# Day.net
KiCad netlist of a schematic drawn in Altium Designer
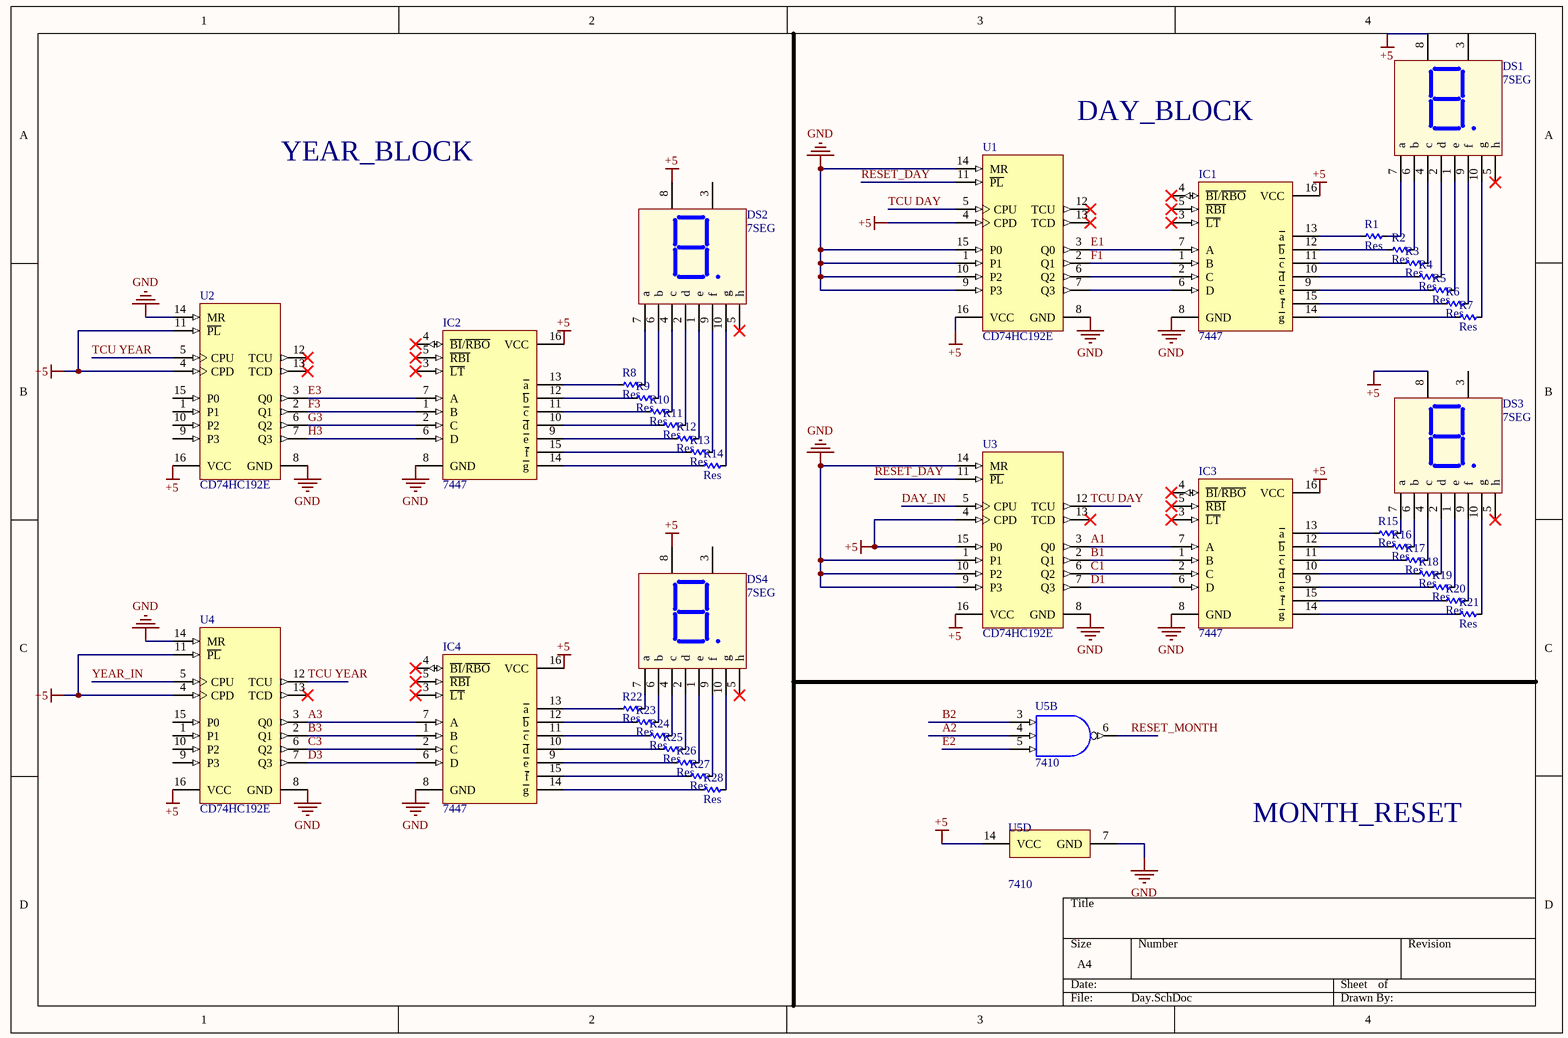
[diagram p0: Day.SchDoc]

(export (version "E")
  (design (tool "Eeschema 10.0.6"))
  (components
    (comp (ref "DS1")
      (value "7SEG")
      (footprint "LED7SEG-1-0.56")
      (description "14.2 mm General Purpose Blue 7-Segment Display: CC, RH DP, Gray Surface")
      (fields (field (name "PUBLISHER") "Altium Limited"))
      (libsource (lib "Clock_Schlib1") (part "LED7SEG-1"))
    )
    (comp (ref "DS2")
      (value "7SEG")
      (footprint "LED7SEG-1-0.56")
      (description "14.2 mm General Purpose Blue 7-Segment Display: CC, RH DP, Gray Surface")
      (fields (field (name "PUBLISHER") "Altium Limited"))
      (libsource (lib "Clock_Schlib1") (part "LED7SEG-1"))
    )
    (comp (ref "DS3")
      (value "7SEG")
      (footprint "LED7SEG-1-0.56")
      (description "14.2 mm General Purpose Blue 7-Segment Display: CC, RH DP, Gray Surface")
      (fields (field (name "PUBLISHER") "Altium Limited"))
      (libsource (lib "Clock_Schlib1") (part "LED7SEG-1"))
    )
    (comp (ref "DS4")
      (value "7SEG")
      (footprint "LED7SEG-1-0.56")
      (description "14.2 mm General Purpose Blue 7-Segment Display: CC, RH DP, Gray Surface")
      (fields (field (name "PUBLISHER") "Altium Limited"))
      (libsource (lib "Clock_Schlib1") (part "LED7SEG-1"))
    )
    (comp (ref "IC1")
      (value "7447")
      (footprint "DIP16")
      (description "BCD to 7-Segment Decoder/Driver")
      (libsource (lib "Clock_Schlib1") (part "7447"))
    )
    (comp (ref "IC2")
      (value "7447")
      (footprint "DIP16")
      (description "BCD to 7-Segment Decoder/Driver")
      (libsource (lib "Clock_Schlib1") (part "7447"))
    )
    (comp (ref "IC3")
      (value "7447")
      (footprint "DIP16")
      (description "BCD to 7-Segment Decoder/Driver")
      (libsource (lib "Clock_Schlib1") (part "7447"))
    )
    (comp (ref "IC4")
      (value "7447")
      (footprint "DIP16")
      (description "BCD to 7-Segment Decoder/Driver")
      (libsource (lib "Clock_Schlib1") (part "7447"))
    )
    (comp (ref "R1")
      (value "Res")
      (footprint "RES-1/4W")
      (fields
        (field (name "MANUFACTURER") "Generic Components")
        (field (name "PUBLISHER") "Altium Hobart Technology Centre")
      )
      (libsource (lib "Clock_Schlib1") (part "Res"))
    )
    (comp (ref "R2")
      (value "Res")
      (footprint "RES-1/4W")
      (fields
        (field (name "MANUFACTURER") "Generic Components")
        (field (name "PUBLISHER") "Altium Hobart Technology Centre")
      )
      (libsource (lib "Clock_Schlib1") (part "Res"))
    )
    (comp (ref "R3")
      (value "Res")
      (footprint "RES-1/4W")
      (fields
        (field (name "MANUFACTURER") "Generic Components")
        (field (name "PUBLISHER") "Altium Hobart Technology Centre")
      )
      (libsource (lib "Clock_Schlib1") (part "Res"))
    )
    (comp (ref "R4")
      (value "Res")
      (footprint "RES-1/4W")
      (fields
        (field (name "MANUFACTURER") "Generic Components")
        (field (name "PUBLISHER") "Altium Hobart Technology Centre")
      )
      (libsource (lib "Clock_Schlib1") (part "Res"))
    )
    (comp (ref "R5")
      (value "Res")
      (footprint "RES-1/4W")
      (fields
        (field (name "MANUFACTURER") "Generic Components")
        (field (name "PUBLISHER") "Altium Hobart Technology Centre")
      )
      (libsource (lib "Clock_Schlib1") (part "Res"))
    )
    (comp (ref "R6")
      (value "Res")
      (footprint "RES-1/4W")
      (fields
        (field (name "MANUFACTURER") "Generic Components")
        (field (name "PUBLISHER") "Altium Hobart Technology Centre")
      )
      (libsource (lib "Clock_Schlib1") (part "Res"))
    )
    (comp (ref "R7")
      (value "Res")
      (footprint "RES-1/4W")
      (fields
        (field (name "MANUFACTURER") "Generic Components")
        (field (name "PUBLISHER") "Altium Hobart Technology Centre")
      )
      (libsource (lib "Clock_Schlib1") (part "Res"))
    )
    (comp (ref "R8")
      (value "Res")
      (footprint "RES-1/4W")
      (fields
        (field (name "MANUFACTURER") "Generic Components")
        (field (name "PUBLISHER") "Altium Hobart Technology Centre")
      )
      (libsource (lib "Clock_Schlib1") (part "Res"))
    )
    (comp (ref "R9")
      (value "Res")
      (footprint "RES-1/4W")
      (fields
        (field (name "MANUFACTURER") "Generic Components")
        (field (name "PUBLISHER") "Altium Hobart Technology Centre")
      )
      (libsource (lib "Clock_Schlib1") (part "Res"))
    )
    (comp (ref "R10")
      (value "Res")
      (footprint "RES-1/4W")
      (fields
        (field (name "MANUFACTURER") "Generic Components")
        (field (name "PUBLISHER") "Altium Hobart Technology Centre")
      )
      (libsource (lib "Clock_Schlib1") (part "Res"))
    )
    (comp (ref "R11")
      (value "Res")
      (footprint "RES-1/4W")
      (fields
        (field (name "MANUFACTURER") "Generic Components")
        (field (name "PUBLISHER") "Altium Hobart Technology Centre")
      )
      (libsource (lib "Clock_Schlib1") (part "Res"))
    )
    (comp (ref "R12")
      (value "Res")
      (footprint "RES-1/4W")
      (fields
        (field (name "MANUFACTURER") "Generic Components")
        (field (name "PUBLISHER") "Altium Hobart Technology Centre")
      )
      (libsource (lib "Clock_Schlib1") (part "Res"))
    )
    (comp (ref "R13")
      (value "Res")
      (footprint "RES-1/4W")
      (fields
        (field (name "MANUFACTURER") "Generic Components")
        (field (name "PUBLISHER") "Altium Hobart Technology Centre")
      )
      (libsource (lib "Clock_Schlib1") (part "Res"))
    )
    (comp (ref "R14")
      (value "Res")
      (footprint "RES-1/4W")
      (fields
        (field (name "MANUFACTURER") "Generic Components")
        (field (name "PUBLISHER") "Altium Hobart Technology Centre")
      )
      (libsource (lib "Clock_Schlib1") (part "Res"))
    )
    (comp (ref "R15")
      (value "Res")
      (footprint "RES-1/4W")
      (fields
        (field (name "MANUFACTURER") "Generic Components")
        (field (name "PUBLISHER") "Altium Hobart Technology Centre")
      )
      (libsource (lib "Clock_Schlib1") (part "Res"))
    )
    (comp (ref "R16")
      (value "Res")
      (footprint "RES-1/4W")
      (fields
        (field (name "MANUFACTURER") "Generic Components")
        (field (name "PUBLISHER") "Altium Hobart Technology Centre")
      )
      (libsource (lib "Clock_Schlib1") (part "Res"))
    )
    (comp (ref "R17")
      (value "Res")
      (footprint "RES-1/4W")
      (fields
        (field (name "MANUFACTURER") "Generic Components")
        (field (name "PUBLISHER") "Altium Hobart Technology Centre")
      )
      (libsource (lib "Clock_Schlib1") (part "Res"))
    )
    (comp (ref "R18")
      (value "Res")
      (footprint "RES-1/4W")
      (fields
        (field (name "MANUFACTURER") "Generic Components")
        (field (name "PUBLISHER") "Altium Hobart Technology Centre")
      )
      (libsource (lib "Clock_Schlib1") (part "Res"))
    )
    (comp (ref "R19")
      (value "Res")
      (footprint "RES-1/4W")
      (fields
        (field (name "MANUFACTURER") "Generic Components")
        (field (name "PUBLISHER") "Altium Hobart Technology Centre")
      )
      (libsource (lib "Clock_Schlib1") (part "Res"))
    )
    (comp (ref "R20")
      (value "Res")
      (footprint "RES-1/4W")
      (fields
        (field (name "MANUFACTURER") "Generic Components")
        (field (name "PUBLISHER") "Altium Hobart Technology Centre")
      )
      (libsource (lib "Clock_Schlib1") (part "Res"))
    )
    (comp (ref "R21")
      (value "Res")
      (footprint "RES-1/4W")
      (fields
        (field (name "MANUFACTURER") "Generic Components")
        (field (name "PUBLISHER") "Altium Hobart Technology Centre")
      )
      (libsource (lib "Clock_Schlib1") (part "Res"))
    )
    (comp (ref "R22")
      (value "Res")
      (footprint "RES-1/4W")
      (fields
        (field (name "MANUFACTURER") "Generic Components")
        (field (name "PUBLISHER") "Altium Hobart Technology Centre")
      )
      (libsource (lib "Clock_Schlib1") (part "Res"))
    )
    (comp (ref "R23")
      (value "Res")
      (footprint "RES-1/4W")
      (fields
        (field (name "MANUFACTURER") "Generic Components")
        (field (name "PUBLISHER") "Altium Hobart Technology Centre")
      )
      (libsource (lib "Clock_Schlib1") (part "Res"))
    )
    (comp (ref "R24")
      (value "Res")
      (footprint "RES-1/4W")
      (fields
        (field (name "MANUFACTURER") "Generic Components")
        (field (name "PUBLISHER") "Altium Hobart Technology Centre")
      )
      (libsource (lib "Clock_Schlib1") (part "Res"))
    )
    (comp (ref "R25")
      (value "Res")
      (footprint "RES-1/4W")
      (fields
        (field (name "MANUFACTURER") "Generic Components")
        (field (name "PUBLISHER") "Altium Hobart Technology Centre")
      )
      (libsource (lib "Clock_Schlib1") (part "Res"))
    )
    (comp (ref "R26")
      (value "Res")
      (footprint "RES-1/4W")
      (fields
        (field (name "MANUFACTURER") "Generic Components")
        (field (name "PUBLISHER") "Altium Hobart Technology Centre")
      )
      (libsource (lib "Clock_Schlib1") (part "Res"))
    )
    (comp (ref "R27")
      (value "Res")
      (footprint "RES-1/4W")
      (fields
        (field (name "MANUFACTURER") "Generic Components")
        (field (name "PUBLISHER") "Altium Hobart Technology Centre")
      )
      (libsource (lib "Clock_Schlib1") (part "Res"))
    )
    (comp (ref "R28")
      (value "Res")
      (footprint "RES-1/4W")
      (fields
        (field (name "MANUFACTURER") "Generic Components")
        (field (name "PUBLISHER") "Altium Hobart Technology Centre")
      )
      (libsource (lib "Clock_Schlib1") (part "Res"))
    )
    (comp (ref "U1")
      (value "CD74HC192E")
      (footprint "N0016A")
      (fields
        (field (name "GENERIC PART NUMBER") "CD74HC192")
        (field (name "MANUFACTURER") "Texas Instruments")
      )
      (libsource (lib "Clock_Schlib1") (part "74192"))
    )
    (comp (ref "U2")
      (value "CD74HC192E")
      (footprint "N0016A")
      (fields
        (field (name "GENERIC PART NUMBER") "CD74HC192")
        (field (name "MANUFACTURER") "Texas Instruments")
      )
      (libsource (lib "Clock_Schlib1") (part "74192"))
    )
    (comp (ref "U3")
      (value "CD74HC192E")
      (footprint "N0016A")
      (fields
        (field (name "GENERIC PART NUMBER") "CD74HC192")
        (field (name "MANUFACTURER") "Texas Instruments")
      )
      (libsource (lib "Clock_Schlib1") (part "74192"))
    )
    (comp (ref "U4")
      (value "CD74HC192E")
      (footprint "N0016A")
      (fields
        (field (name "GENERIC PART NUMBER") "CD74HC192")
        (field (name "MANUFACTURER") "Texas Instruments")
      )
      (libsource (lib "Clock_Schlib1") (part "74192"))
    )
    (comp (ref "U5")
      (value "7410")
      (footprint "N0014A")
      (description "Triple 3-input positive-NAND gates, N0014A, TUBE")
      (fields
        (field (name "MANUFACTURER") "Texas Instruments")
        (field (name "GENERIC PART NUMBER") "SN74F10")
      )
      (libsource (lib "Clock_Schlib1") (part "7410"))
    )
  )
  (nets
    (net (code "1") (name "+5") (class "Default")
      (node (ref "DS1") (pin "8") (pinfunction "Vcc_8") (pintype "passive"))
      (node (ref "DS2") (pin "8") (pinfunction "Vcc_8") (pintype "passive"))
      (node (ref "DS3") (pin "8") (pinfunction "Vcc_8") (pintype "passive"))
      (node (ref "DS4") (pin "8") (pinfunction "Vcc_8") (pintype "passive"))
      (node (ref "IC1") (pin "16") (pinfunction "VCC_16") (pintype "power_in"))
      (node (ref "IC2") (pin "16") (pinfunction "VCC_16") (pintype "power_in"))
      (node (ref "IC3") (pin "16") (pinfunction "VCC_16") (pintype "power_in"))
      (node (ref "IC4") (pin "16") (pinfunction "VCC_16") (pintype "power_in"))
      (node (ref "U1") (pin "16") (pinfunction "VCC_16") (pintype "power_in"))
      (node (ref "U1") (pin "4") (pinfunction "CPD_4") (pintype "input"))
      (node (ref "U2") (pin "11") (pinfunction "~{PL}_11") (pintype "input"))
      (node (ref "U2") (pin "16") (pinfunction "VCC_16") (pintype "power_in"))
      (node (ref "U2") (pin "4") (pinfunction "CPD_4") (pintype "input"))
      (node (ref "U3") (pin "15") (pinfunction "P0_15") (pintype "input"))
      (node (ref "U3") (pin "16") (pinfunction "VCC_16") (pintype "power_in"))
      (node (ref "U3") (pin "4") (pinfunction "CPD_4") (pintype "input"))
      (node (ref "U4") (pin "11") (pinfunction "~{PL}_11") (pintype "input"))
      (node (ref "U4") (pin "16") (pinfunction "VCC_16") (pintype "power_in"))
      (node (ref "U4") (pin "4") (pinfunction "CPD_4") (pintype "input"))
      (node (ref "U5") (pin "14") (pinfunction "VCC_14") (pintype "power_in"))
    )
    (net (code "2") (name "/A1") (class "Default")
      (node (ref "IC3") (pin "7") (pinfunction "A_7") (pintype "input"))
      (node (ref "U3") (pin "3") (pinfunction "Q0_3") (pintype "output"))
    )
    (net (code "3") (name "/A2") (class "Default")
      (node (ref "U5") (pin "4") (pinfunction "2B_4") (pintype "input"))
    )
    (net (code "4") (name "/A3") (class "Default")
      (node (ref "IC4") (pin "7") (pinfunction "A_7") (pintype "input"))
      (node (ref "U4") (pin "3") (pinfunction "Q0_3") (pintype "output"))
    )
    (net (code "5") (name "/B1") (class "Default")
      (node (ref "IC3") (pin "1") (pinfunction "B_1") (pintype "input"))
      (node (ref "U3") (pin "2") (pinfunction "Q1_2") (pintype "output"))
    )
    (net (code "6") (name "/B2") (class "Default")
      (node (ref "U5") (pin "3") (pinfunction "2A_3") (pintype "input"))
    )
    (net (code "7") (name "/B3") (class "Default")
      (node (ref "IC4") (pin "1") (pinfunction "B_1") (pintype "input"))
      (node (ref "U4") (pin "2") (pinfunction "Q1_2") (pintype "output"))
    )
    (net (code "8") (name "/C1") (class "Default")
      (node (ref "IC3") (pin "2") (pinfunction "C_2") (pintype "input"))
      (node (ref "U3") (pin "6") (pinfunction "Q2_6") (pintype "output"))
    )
    (net (code "9") (name "/C3") (class "Default")
      (node (ref "IC4") (pin "2") (pinfunction "C_2") (pintype "input"))
      (node (ref "U4") (pin "6") (pinfunction "Q2_6") (pintype "output"))
    )
    (net (code "10") (name "/D1") (class "Default")
      (node (ref "IC3") (pin "6") (pinfunction "D_6") (pintype "input"))
      (node (ref "U3") (pin "7") (pinfunction "Q3_7") (pintype "output"))
    )
    (net (code "11") (name "/D3") (class "Default")
      (node (ref "IC4") (pin "6") (pinfunction "D_6") (pintype "input"))
      (node (ref "U4") (pin "7") (pinfunction "Q3_7") (pintype "output"))
    )
    (net (code "12") (name "/DAY_IN") (class "Default")
      (node (ref "U3") (pin "5") (pinfunction "CPU_5") (pintype "input"))
    )
    (net (code "13") (name "/E1") (class "Default")
      (node (ref "IC1") (pin "7") (pinfunction "A_7") (pintype "input"))
      (node (ref "U1") (pin "3") (pinfunction "Q0_3") (pintype "output"))
    )
    (net (code "14") (name "/E2") (class "Default")
      (node (ref "U5") (pin "5") (pinfunction "2C_5") (pintype "input"))
    )
    (net (code "15") (name "/E3") (class "Default")
      (node (ref "IC2") (pin "7") (pinfunction "A_7") (pintype "input"))
      (node (ref "U2") (pin "3") (pinfunction "Q0_3") (pintype "output"))
    )
    (net (code "16") (name "/F1") (class "Default")
      (node (ref "IC1") (pin "1") (pinfunction "B_1") (pintype "input"))
      (node (ref "U1") (pin "2") (pinfunction "Q1_2") (pintype "output"))
    )
    (net (code "17") (name "/F3") (class "Default")
      (node (ref "IC2") (pin "1") (pinfunction "B_1") (pintype "input"))
      (node (ref "U2") (pin "2") (pinfunction "Q1_2") (pintype "output"))
    )
    (net (code "18") (name "/G3") (class "Default")
      (node (ref "IC2") (pin "2") (pinfunction "C_2") (pintype "input"))
      (node (ref "U2") (pin "6") (pinfunction "Q2_6") (pintype "output"))
    )
    (net (code "19") (name "/H3") (class "Default")
      (node (ref "IC2") (pin "6") (pinfunction "D_6") (pintype "input"))
      (node (ref "U2") (pin "7") (pinfunction "Q3_7") (pintype "output"))
    )
    (net (code "20") (name "/RESET_DAY") (class "Default")
      (node (ref "U1") (pin "11") (pinfunction "~{PL}_11") (pintype "input"))
      (node (ref "U3") (pin "11") (pinfunction "~{PL}_11") (pintype "input"))
    )
    (net (code "21") (name "/RESET_MONTH") (class "Default")
      (node (ref "U5") (pin "6") (pinfunction "2Y_6") (pintype "output"))
    )
    (net (code "22") (name "/TCU DAY") (class "Default")
      (node (ref "U1") (pin "5") (pinfunction "CPU_5") (pintype "input"))
      (node (ref "U3") (pin "12") (pinfunction "TCU_12") (pintype "output"))
    )
    (net (code "23") (name "/TCU YEAR") (class "Default")
      (node (ref "U2") (pin "5") (pinfunction "CPU_5") (pintype "input"))
      (node (ref "U4") (pin "12") (pinfunction "TCU_12") (pintype "output"))
    )
    (net (code "24") (name "/YEAR_IN") (class "Default")
      (node (ref "U4") (pin "5") (pinfunction "CPU_5") (pintype "input"))
    )
    (net (code "25") (name "GND") (class "Default")
      (node (ref "IC1") (pin "8") (pinfunction "GND_8") (pintype "power_in"))
      (node (ref "IC2") (pin "8") (pinfunction "GND_8") (pintype "power_in"))
      (node (ref "IC3") (pin "8") (pinfunction "GND_8") (pintype "power_in"))
      (node (ref "IC4") (pin "8") (pinfunction "GND_8") (pintype "power_in"))
      (node (ref "U1") (pin "1") (pinfunction "P1_1") (pintype "input"))
      (node (ref "U1") (pin "10") (pinfunction "P2_10") (pintype "input"))
      (node (ref "U1") (pin "14") (pinfunction "MR_14") (pintype "input"))
      (node (ref "U1") (pin "15") (pinfunction "P0_15") (pintype "input"))
      (node (ref "U1") (pin "8") (pinfunction "GND_8") (pintype "power_in"))
      (node (ref "U1") (pin "9") (pinfunction "P3_9") (pintype "input"))
      (node (ref "U2") (pin "14") (pinfunction "MR_14") (pintype "input"))
      (node (ref "U2") (pin "8") (pinfunction "GND_8") (pintype "power_in"))
      (node (ref "U3") (pin "1") (pinfunction "P1_1") (pintype "input"))
      (node (ref "U3") (pin "10") (pinfunction "P2_10") (pintype "input"))
      (node (ref "U3") (pin "14") (pinfunction "MR_14") (pintype "input"))
      (node (ref "U3") (pin "8") (pinfunction "GND_8") (pintype "power_in"))
      (node (ref "U3") (pin "9") (pinfunction "P3_9") (pintype "input"))
      (node (ref "U4") (pin "14") (pinfunction "MR_14") (pintype "input"))
      (node (ref "U4") (pin "8") (pinfunction "GND_8") (pintype "power_in"))
      (node (ref "U5") (pin "7") (pinfunction "GND_7") (pintype "power_in"))
    )
    (net (code "26") (name "Net-(DS1-a)") (class "Default")
      (node (ref "DS1") (pin "7") (pinfunction "a_7") (pintype "passive"))
      (node (ref "R1") (pin "1") (pinfunction "1_1") (pintype "passive"))
    )
    (net (code "27") (name "Net-(DS1-b)") (class "Default")
      (node (ref "DS1") (pin "6") (pinfunction "b_6") (pintype "passive"))
      (node (ref "R2") (pin "1") (pinfunction "1_1") (pintype "passive"))
    )
    (net (code "28") (name "Net-(DS1-c)") (class "Default")
      (node (ref "DS1") (pin "4") (pinfunction "c_4") (pintype "passive"))
      (node (ref "R3") (pin "1") (pinfunction "1_1") (pintype "passive"))
    )
    (net (code "29") (name "Net-(DS1-d)") (class "Default")
      (node (ref "DS1") (pin "2") (pinfunction "d_2") (pintype "passive"))
      (node (ref "R4") (pin "1") (pinfunction "1_1") (pintype "passive"))
    )
    (net (code "30") (name "Net-(DS1-e)") (class "Default")
      (node (ref "DS1") (pin "1") (pinfunction "e_1") (pintype "passive"))
      (node (ref "R5") (pin "1") (pinfunction "1_1") (pintype "passive"))
    )
    (net (code "31") (name "Net-(DS1-f)") (class "Default")
      (node (ref "DS1") (pin "9") (pinfunction "f_9") (pintype "passive"))
      (node (ref "R6") (pin "1") (pinfunction "1_1") (pintype "passive"))
    )
    (net (code "32") (name "Net-(DS1-g)") (class "Default")
      (node (ref "DS1") (pin "10") (pinfunction "g_10") (pintype "passive"))
      (node (ref "R7") (pin "1") (pinfunction "1_1") (pintype "passive"))
    )
    (net (code "33") (name "Net-(DS2-a)") (class "Default")
      (node (ref "DS2") (pin "7") (pinfunction "a_7") (pintype "passive"))
      (node (ref "R8") (pin "1") (pinfunction "1_1") (pintype "passive"))
    )
    (net (code "34") (name "Net-(DS2-b)") (class "Default")
      (node (ref "DS2") (pin "6") (pinfunction "b_6") (pintype "passive"))
      (node (ref "R9") (pin "1") (pinfunction "1_1") (pintype "passive"))
    )
    (net (code "35") (name "Net-(DS2-c)") (class "Default")
      (node (ref "DS2") (pin "4") (pinfunction "c_4") (pintype "passive"))
      (node (ref "R10") (pin "1") (pinfunction "1_1") (pintype "passive"))
    )
    (net (code "36") (name "Net-(DS2-d)") (class "Default")
      (node (ref "DS2") (pin "2") (pinfunction "d_2") (pintype "passive"))
      (node (ref "R11") (pin "1") (pinfunction "1_1") (pintype "passive"))
    )
    (net (code "37") (name "Net-(DS2-e)") (class "Default")
      (node (ref "DS2") (pin "1") (pinfunction "e_1") (pintype "passive"))
      (node (ref "R12") (pin "1") (pinfunction "1_1") (pintype "passive"))
    )
    (net (code "38") (name "Net-(DS2-f)") (class "Default")
      (node (ref "DS2") (pin "9") (pinfunction "f_9") (pintype "passive"))
      (node (ref "R13") (pin "1") (pinfunction "1_1") (pintype "passive"))
    )
    (net (code "39") (name "Net-(DS2-g)") (class "Default")
      (node (ref "DS2") (pin "10") (pinfunction "g_10") (pintype "passive"))
      (node (ref "R14") (pin "1") (pinfunction "1_1") (pintype "passive"))
    )
    (net (code "40") (name "Net-(DS3-a)") (class "Default")
      (node (ref "DS3") (pin "7") (pinfunction "a_7") (pintype "passive"))
      (node (ref "R15") (pin "1") (pinfunction "1_1") (pintype "passive"))
    )
    (net (code "41") (name "Net-(DS3-b)") (class "Default")
      (node (ref "DS3") (pin "6") (pinfunction "b_6") (pintype "passive"))
      (node (ref "R16") (pin "1") (pinfunction "1_1") (pintype "passive"))
    )
    (net (code "42") (name "Net-(DS3-c)") (class "Default")
      (node (ref "DS3") (pin "4") (pinfunction "c_4") (pintype "passive"))
      (node (ref "R17") (pin "1") (pinfunction "1_1") (pintype "passive"))
    )
    (net (code "43") (name "Net-(DS3-d)") (class "Default")
      (node (ref "DS3") (pin "2") (pinfunction "d_2") (pintype "passive"))
      (node (ref "R18") (pin "1") (pinfunction "1_1") (pintype "passive"))
    )
    (net (code "44") (name "Net-(DS3-e)") (class "Default")
      (node (ref "DS3") (pin "1") (pinfunction "e_1") (pintype "passive"))
      (node (ref "R19") (pin "1") (pinfunction "1_1") (pintype "passive"))
    )
    (net (code "45") (name "Net-(DS3-f)") (class "Default")
      (node (ref "DS3") (pin "9") (pinfunction "f_9") (pintype "passive"))
      (node (ref "R20") (pin "1") (pinfunction "1_1") (pintype "passive"))
    )
    (net (code "46") (name "Net-(DS3-g)") (class "Default")
      (node (ref "DS3") (pin "10") (pinfunction "g_10") (pintype "passive"))
      (node (ref "R21") (pin "1") (pinfunction "1_1") (pintype "passive"))
    )
    (net (code "47") (name "Net-(DS4-a)") (class "Default")
      (node (ref "DS4") (pin "7") (pinfunction "a_7") (pintype "passive"))
      (node (ref "R22") (pin "1") (pinfunction "1_1") (pintype "passive"))
    )
    (net (code "48") (name "Net-(DS4-b)") (class "Default")
      (node (ref "DS4") (pin "6") (pinfunction "b_6") (pintype "passive"))
      (node (ref "R23") (pin "1") (pinfunction "1_1") (pintype "passive"))
    )
    (net (code "49") (name "Net-(DS4-c)") (class "Default")
      (node (ref "DS4") (pin "4") (pinfunction "c_4") (pintype "passive"))
      (node (ref "R24") (pin "1") (pinfunction "1_1") (pintype "passive"))
    )
    (net (code "50") (name "Net-(DS4-d)") (class "Default")
      (node (ref "DS4") (pin "2") (pinfunction "d_2") (pintype "passive"))
      (node (ref "R25") (pin "1") (pinfunction "1_1") (pintype "passive"))
    )
    (net (code "51") (name "Net-(DS4-e)") (class "Default")
      (node (ref "DS4") (pin "1") (pinfunction "e_1") (pintype "passive"))
      (node (ref "R26") (pin "1") (pinfunction "1_1") (pintype "passive"))
    )
    (net (code "52") (name "Net-(DS4-f)") (class "Default")
      (node (ref "DS4") (pin "9") (pinfunction "f_9") (pintype "passive"))
      (node (ref "R27") (pin "1") (pinfunction "1_1") (pintype "passive"))
    )
    (net (code "53") (name "Net-(DS4-g)") (class "Default")
      (node (ref "DS4") (pin "10") (pinfunction "g_10") (pintype "passive"))
      (node (ref "R28") (pin "1") (pinfunction "1_1") (pintype "passive"))
    )
    (net (code "54") (name "Net-(IC1-C)") (class "Default")
      (node (ref "IC1") (pin "2") (pinfunction "C_2") (pintype "input"))
      (node (ref "U1") (pin "6") (pinfunction "Q2_6") (pintype "output"))
    )
    (net (code "55") (name "Net-(IC1-D)") (class "Default")
      (node (ref "IC1") (pin "6") (pinfunction "D_6") (pintype "input"))
      (node (ref "U1") (pin "7") (pinfunction "Q3_7") (pintype "output"))
    )
    (net (code "56") (name "Net-(IC1-~{a})") (class "Default")
      (node (ref "IC1") (pin "13") (pinfunction "~{a}_13") (pintype "open_collector"))
      (node (ref "R1") (pin "2") (pinfunction "2_2") (pintype "passive"))
    )
    (net (code "57") (name "Net-(IC1-~{b})") (class "Default")
      (node (ref "IC1") (pin "12") (pinfunction "~{b}_12") (pintype "open_collector"))
      (node (ref "R2") (pin "2") (pinfunction "2_2") (pintype "passive"))
    )
    (net (code "58") (name "Net-(IC1-~{c})") (class "Default")
      (node (ref "IC1") (pin "11") (pinfunction "~{c}_11") (pintype "open_collector"))
      (node (ref "R3") (pin "2") (pinfunction "2_2") (pintype "passive"))
    )
    (net (code "59") (name "Net-(IC1-~{d})") (class "Default")
      (node (ref "IC1") (pin "10") (pinfunction "~{d}_10") (pintype "open_collector"))
      (node (ref "R4") (pin "2") (pinfunction "2_2") (pintype "passive"))
    )
    (net (code "60") (name "Net-(IC1-~{e})") (class "Default")
      (node (ref "IC1") (pin "9") (pinfunction "~{e}_9") (pintype "open_collector"))
      (node (ref "R5") (pin "2") (pinfunction "2_2") (pintype "passive"))
    )
    (net (code "61") (name "Net-(IC1-~{f})") (class "Default")
      (node (ref "IC1") (pin "15") (pinfunction "~{f}_15") (pintype "open_collector"))
      (node (ref "R6") (pin "2") (pinfunction "2_2") (pintype "passive"))
    )
    (net (code "62") (name "Net-(IC1-~{g})") (class "Default")
      (node (ref "IC1") (pin "14") (pinfunction "~{g}_14") (pintype "open_collector"))
      (node (ref "R7") (pin "2") (pinfunction "2_2") (pintype "passive"))
    )
    (net (code "63") (name "Net-(IC2-~{a})") (class "Default")
      (node (ref "IC2") (pin "13") (pinfunction "~{a}_13") (pintype "open_collector"))
      (node (ref "R8") (pin "2") (pinfunction "2_2") (pintype "passive"))
    )
    (net (code "64") (name "Net-(IC2-~{b})") (class "Default")
      (node (ref "IC2") (pin "12") (pinfunction "~{b}_12") (pintype "open_collector"))
      (node (ref "R9") (pin "2") (pinfunction "2_2") (pintype "passive"))
    )
    (net (code "65") (name "Net-(IC2-~{c})") (class "Default")
      (node (ref "IC2") (pin "11") (pinfunction "~{c}_11") (pintype "open_collector"))
      (node (ref "R10") (pin "2") (pinfunction "2_2") (pintype "passive"))
    )
    (net (code "66") (name "Net-(IC2-~{d})") (class "Default")
      (node (ref "IC2") (pin "10") (pinfunction "~{d}_10") (pintype "open_collector"))
      (node (ref "R11") (pin "2") (pinfunction "2_2") (pintype "passive"))
    )
    (net (code "67") (name "Net-(IC2-~{e})") (class "Default")
      (node (ref "IC2") (pin "9") (pinfunction "~{e}_9") (pintype "open_collector"))
      (node (ref "R12") (pin "2") (pinfunction "2_2") (pintype "passive"))
    )
    (net (code "68") (name "Net-(IC2-~{f})") (class "Default")
      (node (ref "IC2") (pin "15") (pinfunction "~{f}_15") (pintype "open_collector"))
      (node (ref "R13") (pin "2") (pinfunction "2_2") (pintype "passive"))
    )
    (net (code "69") (name "Net-(IC2-~{g})") (class "Default")
      (node (ref "IC2") (pin "14") (pinfunction "~{g}_14") (pintype "open_collector"))
      (node (ref "R14") (pin "2") (pinfunction "2_2") (pintype "passive"))
    )
    (net (code "70") (name "Net-(IC3-~{a})") (class "Default")
      (node (ref "IC3") (pin "13") (pinfunction "~{a}_13") (pintype "open_collector"))
      (node (ref "R15") (pin "2") (pinfunction "2_2") (pintype "passive"))
    )
    (net (code "71") (name "Net-(IC3-~{b})") (class "Default")
      (node (ref "IC3") (pin "12") (pinfunction "~{b}_12") (pintype "open_collector"))
      (node (ref "R16") (pin "2") (pinfunction "2_2") (pintype "passive"))
    )
    (net (code "72") (name "Net-(IC3-~{c})") (class "Default")
      (node (ref "IC3") (pin "11") (pinfunction "~{c}_11") (pintype "open_collector"))
      (node (ref "R17") (pin "2") (pinfunction "2_2") (pintype "passive"))
    )
    (net (code "73") (name "Net-(IC3-~{d})") (class "Default")
      (node (ref "IC3") (pin "10") (pinfunction "~{d}_10") (pintype "open_collector"))
      (node (ref "R18") (pin "2") (pinfunction "2_2") (pintype "passive"))
    )
    (net (code "74") (name "Net-(IC3-~{e})") (class "Default")
      (node (ref "IC3") (pin "9") (pinfunction "~{e}_9") (pintype "open_collector"))
      (node (ref "R19") (pin "2") (pinfunction "2_2") (pintype "passive"))
    )
    (net (code "75") (name "Net-(IC3-~{f})") (class "Default")
      (node (ref "IC3") (pin "15") (pinfunction "~{f}_15") (pintype "open_collector"))
      (node (ref "R20") (pin "2") (pinfunction "2_2") (pintype "passive"))
    )
    (net (code "76") (name "Net-(IC3-~{g})") (class "Default")
      (node (ref "IC3") (pin "14") (pinfunction "~{g}_14") (pintype "open_collector"))
      (node (ref "R21") (pin "2") (pinfunction "2_2") (pintype "passive"))
    )
    (net (code "77") (name "Net-(IC4-~{a})") (class "Default")
      (node (ref "IC4") (pin "13") (pinfunction "~{a}_13") (pintype "open_collector"))
      (node (ref "R22") (pin "2") (pinfunction "2_2") (pintype "passive"))
    )
    (net (code "78") (name "Net-(IC4-~{b})") (class "Default")
      (node (ref "IC4") (pin "12") (pinfunction "~{b}_12") (pintype "open_collector"))
      (node (ref "R23") (pin "2") (pinfunction "2_2") (pintype "passive"))
    )
    (net (code "79") (name "Net-(IC4-~{c})") (class "Default")
      (node (ref "IC4") (pin "11") (pinfunction "~{c}_11") (pintype "open_collector"))
      (node (ref "R24") (pin "2") (pinfunction "2_2") (pintype "passive"))
    )
    (net (code "80") (name "Net-(IC4-~{d})") (class "Default")
      (node (ref "IC4") (pin "10") (pinfunction "~{d}_10") (pintype "open_collector"))
      (node (ref "R25") (pin "2") (pinfunction "2_2") (pintype "passive"))
    )
    (net (code "81") (name "Net-(IC4-~{e})") (class "Default")
      (node (ref "IC4") (pin "9") (pinfunction "~{e}_9") (pintype "open_collector"))
      (node (ref "R26") (pin "2") (pinfunction "2_2") (pintype "passive"))
    )
    (net (code "82") (name "Net-(IC4-~{f})") (class "Default")
      (node (ref "IC4") (pin "15") (pinfunction "~{f}_15") (pintype "open_collector"))
      (node (ref "R27") (pin "2") (pinfunction "2_2") (pintype "passive"))
    )
    (net (code "83") (name "Net-(IC4-~{g})") (class "Default")
      (node (ref "IC4") (pin "14") (pinfunction "~{g}_14") (pintype "open_collector"))
      (node (ref "R28") (pin "2") (pinfunction "2_2") (pintype "passive"))
    )
    (net (code "84") (name "unconnected-(DS1-Vcc-Pad3)") (class "Default")
      (node (ref "DS1") (pin "3") (pinfunction "Vcc_3") (pintype "passive"))
    )
    (net (code "85") (name "unconnected-(DS1-h-Pad5)") (class "Default")
      (node (ref "DS1") (pin "5") (pinfunction "h_5") (pintype "passive+no_connect"))
    )
    (net (code "86") (name "unconnected-(DS2-Vcc-Pad3)") (class "Default")
      (node (ref "DS2") (pin "3") (pinfunction "Vcc_3") (pintype "passive"))
    )
    (net (code "87") (name "unconnected-(DS2-h-Pad5)") (class "Default")
      (node (ref "DS2") (pin "5") (pinfunction "h_5") (pintype "passive+no_connect"))
    )
    (net (code "88") (name "unconnected-(DS3-Vcc-Pad3)") (class "Default")
      (node (ref "DS3") (pin "3") (pinfunction "Vcc_3") (pintype "passive"))
    )
    (net (code "89") (name "unconnected-(DS3-h-Pad5)") (class "Default")
      (node (ref "DS3") (pin "5") (pinfunction "h_5") (pintype "passive+no_connect"))
    )
    (net (code "90") (name "unconnected-(DS4-Vcc-Pad3)") (class "Default")
      (node (ref "DS4") (pin "3") (pinfunction "Vcc_3") (pintype "passive"))
    )
    (net (code "91") (name "unconnected-(DS4-h-Pad5)") (class "Default")
      (node (ref "DS4") (pin "5") (pinfunction "h_5") (pintype "passive+no_connect"))
    )
    (net (code "92") (name "unconnected-(IC1-~{BI}{slash}~{RBO}-Pad4)") (class "Default")
      (node (ref "IC1") (pin "4") (pinfunction "~{BI}/~{RBO}_4") (pintype "bidirectional+no_connect"))
    )
    (net (code "93") (name "unconnected-(IC1-~{LT}-Pad3)") (class "Default")
      (node (ref "IC1") (pin "3") (pinfunction "~{LT}_3") (pintype "input+no_connect"))
    )
    (net (code "94") (name "unconnected-(IC1-~{RBI}-Pad5)") (class "Default")
      (node (ref "IC1") (pin "5") (pinfunction "~{RBI}_5") (pintype "input+no_connect"))
    )
    (net (code "95") (name "unconnected-(IC2-~{BI}{slash}~{RBO}-Pad4)") (class "Default")
      (node (ref "IC2") (pin "4") (pinfunction "~{BI}/~{RBO}_4") (pintype "bidirectional+no_connect"))
    )
    (net (code "96") (name "unconnected-(IC2-~{LT}-Pad3)") (class "Default")
      (node (ref "IC2") (pin "3") (pinfunction "~{LT}_3") (pintype "input+no_connect"))
    )
    (net (code "97") (name "unconnected-(IC2-~{RBI}-Pad5)") (class "Default")
      (node (ref "IC2") (pin "5") (pinfunction "~{RBI}_5") (pintype "input+no_connect"))
    )
    (net (code "98") (name "unconnected-(IC3-~{BI}{slash}~{RBO}-Pad4)") (class "Default")
      (node (ref "IC3") (pin "4") (pinfunction "~{BI}/~{RBO}_4") (pintype "bidirectional+no_connect"))
    )
    (net (code "99") (name "unconnected-(IC3-~{LT}-Pad3)") (class "Default")
      (node (ref "IC3") (pin "3") (pinfunction "~{LT}_3") (pintype "input+no_connect"))
    )
    (net (code "100") (name "unconnected-(IC3-~{RBI}-Pad5)") (class "Default")
      (node (ref "IC3") (pin "5") (pinfunction "~{RBI}_5") (pintype "input+no_connect"))
    )
    (net (code "101") (name "unconnected-(IC4-~{BI}{slash}~{RBO}-Pad4)") (class "Default")
      (node (ref "IC4") (pin "4") (pinfunction "~{BI}/~{RBO}_4") (pintype "bidirectional+no_connect"))
    )
    (net (code "102") (name "unconnected-(IC4-~{LT}-Pad3)") (class "Default")
      (node (ref "IC4") (pin "3") (pinfunction "~{LT}_3") (pintype "input+no_connect"))
    )
    (net (code "103") (name "unconnected-(IC4-~{RBI}-Pad5)") (class "Default")
      (node (ref "IC4") (pin "5") (pinfunction "~{RBI}_5") (pintype "input+no_connect"))
    )
    (net (code "104") (name "unconnected-(U1-TCD-Pad13)") (class "Default")
      (node (ref "U1") (pin "13") (pinfunction "TCD_13") (pintype "output+no_connect"))
    )
    (net (code "105") (name "unconnected-(U1-TCU-Pad12)") (class "Default")
      (node (ref "U1") (pin "12") (pinfunction "TCU_12") (pintype "output+no_connect"))
    )
    (net (code "106") (name "unconnected-(U2-P0-Pad15)") (class "Default")
      (node (ref "U2") (pin "15") (pinfunction "P0_15") (pintype "input"))
    )
    (net (code "107") (name "unconnected-(U2-P1-Pad1)") (class "Default")
      (node (ref "U2") (pin "1") (pinfunction "P1_1") (pintype "input"))
    )
    (net (code "108") (name "unconnected-(U2-P2-Pad10)") (class "Default")
      (node (ref "U2") (pin "10") (pinfunction "P2_10") (pintype "input"))
    )
    (net (code "109") (name "unconnected-(U2-P3-Pad9)") (class "Default")
      (node (ref "U2") (pin "9") (pinfunction "P3_9") (pintype "input"))
    )
    (net (code "110") (name "unconnected-(U2-TCD-Pad13)") (class "Default")
      (node (ref "U2") (pin "13") (pinfunction "TCD_13") (pintype "output+no_connect"))
    )
    (net (code "111") (name "unconnected-(U2-TCU-Pad12)") (class "Default")
      (node (ref "U2") (pin "12") (pinfunction "TCU_12") (pintype "output+no_connect"))
    )
    (net (code "112") (name "unconnected-(U3-TCD-Pad13)") (class "Default")
      (node (ref "U3") (pin "13") (pinfunction "TCD_13") (pintype "output+no_connect"))
    )
    (net (code "113") (name "unconnected-(U4-P0-Pad15)") (class "Default")
      (node (ref "U4") (pin "15") (pinfunction "P0_15") (pintype "input"))
    )
    (net (code "114") (name "unconnected-(U4-P1-Pad1)") (class "Default")
      (node (ref "U4") (pin "1") (pinfunction "P1_1") (pintype "input"))
    )
    (net (code "115") (name "unconnected-(U4-P2-Pad10)") (class "Default")
      (node (ref "U4") (pin "10") (pinfunction "P2_10") (pintype "input"))
    )
    (net (code "116") (name "unconnected-(U4-P3-Pad9)") (class "Default")
      (node (ref "U4") (pin "9") (pinfunction "P3_9") (pintype "input"))
    )
    (net (code "117") (name "unconnected-(U4-TCD-Pad13)") (class "Default")
      (node (ref "U4") (pin "13") (pinfunction "TCD_13") (pintype "output+no_connect"))
    )
  )
)
